# 200_watts_standard_cool_dip.net
KiCad netlist of a schematic drawn in EAGLE
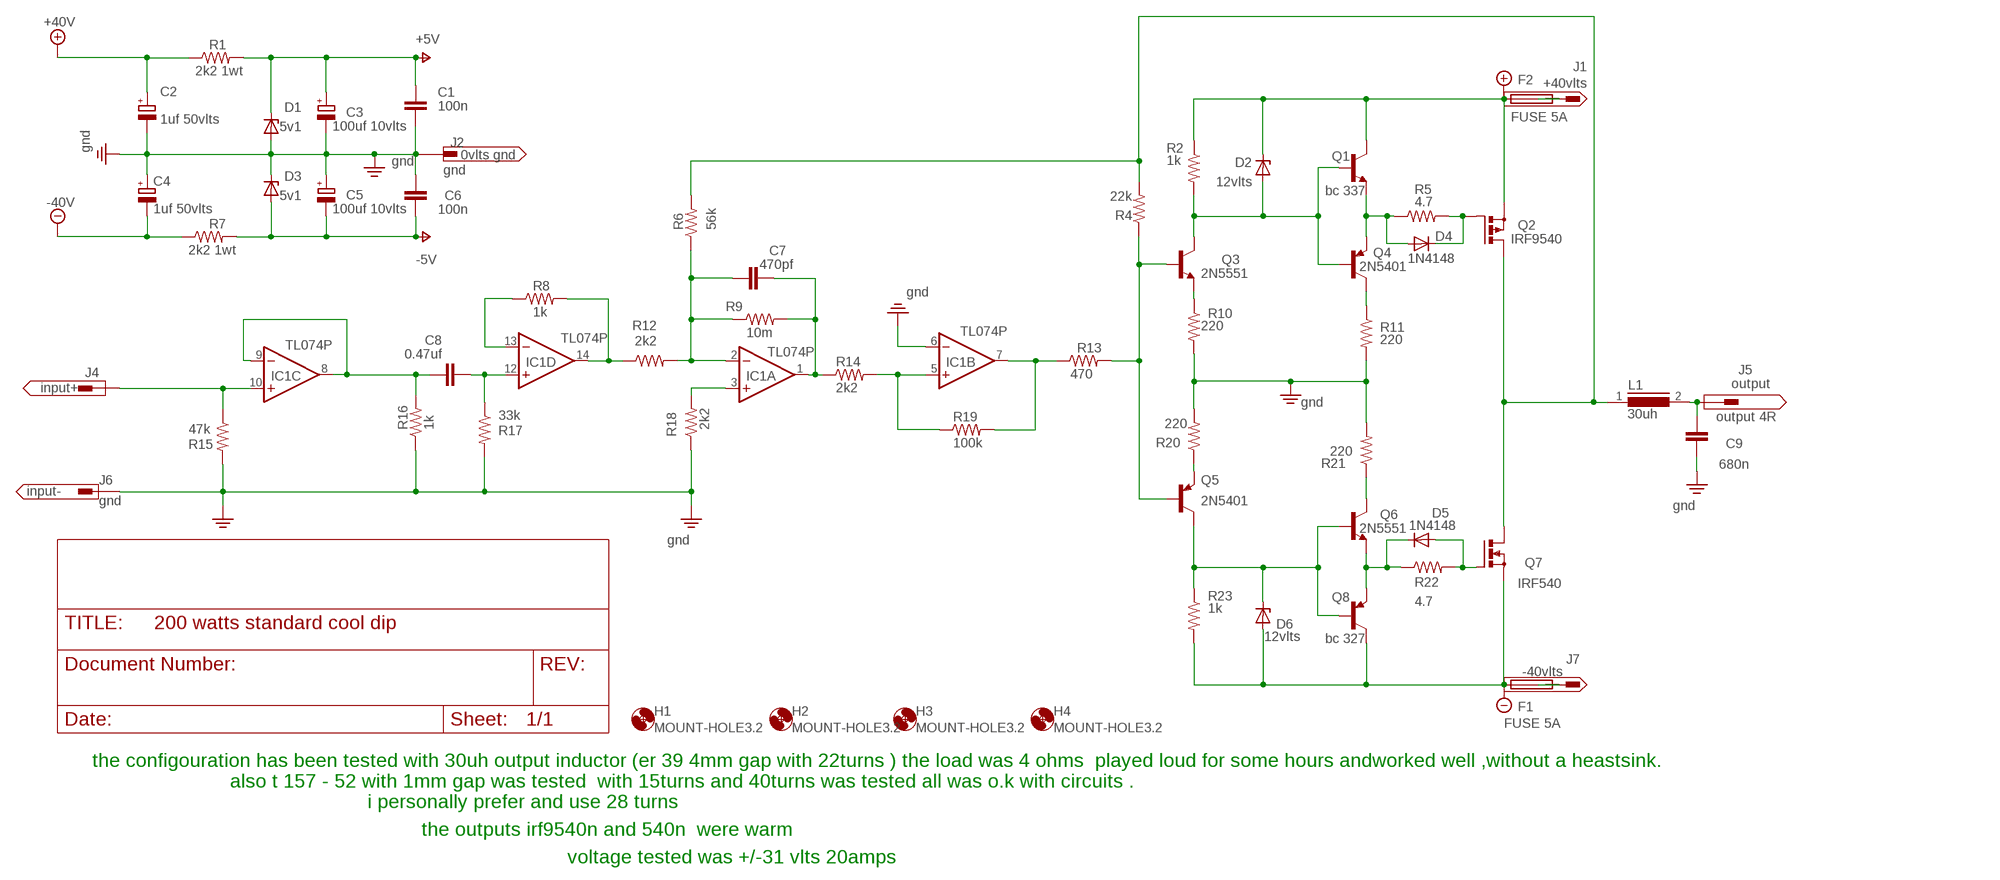
[diagram p0: schematic, sheet 1]

(export (version "E")
  (design (tool "Eeschema 10.0.6"))
  (components
    (comp (ref "C1")
      (value "100n")
      (footprint "eagle-import:C7.5B5")
      (libsource (lib "eagle-import") (part "C7.5/5"))
    )
    (comp (ref "C2")
      (value "1uf 50vlts")
      (footprint "eagle-import:E2,5-6")
      (libsource (lib "eagle-import") (part "CPOL-EUE2.5-6"))
    )
    (comp (ref "C3")
      (value "100uf 10vlts")
      (footprint "eagle-import:E3,5-8")
      (libsource (lib "eagle-import") (part "CPOL-EUE3.5-8"))
    )
    (comp (ref "C4")
      (value "1uf 50vlts")
      (footprint "eagle-import:E2,5-6")
      (libsource (lib "eagle-import") (part "CPOL-EUE2.5-6"))
    )
    (comp (ref "C5")
      (value "100uf 10vlts")
      (footprint "eagle-import:E3,5-8")
      (libsource (lib "eagle-import") (part "CPOL-EUE3.5-8"))
    )
    (comp (ref "C6")
      (value "100n")
      (footprint "eagle-import:C7.5B5")
      (libsource (lib "eagle-import") (part "C7.5/5"))
    )
    (comp (ref "C7")
      (value "470pf")
      (footprint "eagle-import:C5B3.5")
      (libsource (lib "eagle-import") (part "C5/3.5"))
    )
    (comp (ref "C8")
      (value "0.47uf")
      (footprint "eagle-import:C7.5B6")
      (libsource (lib "eagle-import") (part "C7.5/6"))
    )
    (comp (ref "C9")
      (value "680n")
      (footprint "eagle-import:C15B6")
      (libsource (lib "eagle-import") (part "C15/6"))
    )
    (comp (ref "D1")
      (value "5v1")
      (footprint "eagle-import:DO34Z7")
      (libsource (lib "eagle-import") (part "ZENER-DIODEDO34-7"))
    )
    (comp (ref "D2")
      (value "12vlts")
      (footprint "eagle-import:DO34Z7")
      (libsource (lib "eagle-import") (part "ZENER-DIODEDO34-7"))
    )
    (comp (ref "D3")
      (value "5v1")
      (footprint "eagle-import:DO34Z7")
      (libsource (lib "eagle-import") (part "ZENER-DIODEDO34-7"))
    )
    (comp (ref "D4")
      (value "1N4148")
      (footprint "eagle-import:DO35-7")
      (libsource (lib "eagle-import") (part "1N4148DO35-7"))
    )
    (comp (ref "D5")
      (value "1N4148")
      (footprint "eagle-import:DO35-7")
      (libsource (lib "eagle-import") (part "1N4148DO35-7"))
    )
    (comp (ref "D6")
      (value "12vlts")
      (footprint "eagle-import:DO34Z7")
      (libsource (lib "eagle-import") (part "ZENER-DIODEDO34-7"))
    )
    (comp (ref "F1")
      (value "FUSE 5A")
      (footprint "eagle-import:SHK20L")
      (libsource (lib "eagle-import") (part "FUSESHK20L"))
    )
    (comp (ref "F2")
      (value "FUSE 5A")
      (footprint "eagle-import:SHK20L")
      (libsource (lib "eagle-import") (part "FUSESHK20L"))
    )
    (comp (ref "H1")
      (value "MOUNT-HOLE3.2")
      (footprint "eagle-import:3,2")
      (libsource (lib "eagle-import") (part "MOUNT-HOLE3.2"))
    )
    (comp (ref "H2")
      (value "MOUNT-HOLE3.2")
      (footprint "eagle-import:3,2")
      (libsource (lib "eagle-import") (part "MOUNT-HOLE3.2"))
    )
    (comp (ref "H3")
      (value "MOUNT-HOLE3.2")
      (footprint "eagle-import:3,2")
      (libsource (lib "eagle-import") (part "MOUNT-HOLE3.2"))
    )
    (comp (ref "H4")
      (value "MOUNT-HOLE3.2")
      (footprint "eagle-import:3,2")
      (libsource (lib "eagle-import") (part "MOUNT-HOLE3.2"))
    )
    (comp (ref "IC1")
      (value "TL074P")
      (footprint "eagle-import:DIL14")
      (libsource (lib "eagle-import") (part "TL074P"))
    )
    (comp (ref "J1")
      (value "+40v")
      (footprint "eagle-import:F061.040")
      (fields (field (name "OC_FARNELL") "unknown") (field (name "OC_NEWARK") "unknown"))
      (libsource (lib "eagle-import") (part "PIN2F061.040"))
    )
    (comp (ref "J2")
      (value "gnd")
      (footprint "eagle-import:F061.040")
      (fields (field (name "OC_FARNELL") "unknown") (field (name "OC_NEWARK") "unknown"))
      (libsource (lib "eagle-import") (part "PIN2F061.040"))
    )
    (comp (ref "J4")
      (value "input")
      (footprint "eagle-import:F061.040")
      (fields (field (name "OC_FARNELL") "unknown") (field (name "OC_NEWARK") "unknown"))
      (libsource (lib "eagle-import") (part "PIN2F061.040"))
    )
    (comp (ref "J5")
      (value "output")
      (footprint "eagle-import:F061.040")
      (fields (field (name "OC_FARNELL") "unknown") (field (name "OC_NEWARK") "unknown"))
      (libsource (lib "eagle-import") (part "PIN2F061.040"))
    )
    (comp (ref "J6")
      (value "gnd")
      (footprint "eagle-import:F061.040")
      (fields (field (name "OC_FARNELL") "unknown") (field (name "OC_NEWARK") "unknown"))
      (libsource (lib "eagle-import") (part "PIN2F061.040"))
    )
    (comp (ref "J7")
      (value "-40v")
      (footprint "eagle-import:F061.040")
      (fields (field (name "OC_FARNELL") "unknown") (field (name "OC_NEWARK") "unknown"))
      (libsource (lib "eagle-import") (part "PIN2F061.040"))
    )
    (comp (ref "L1")
      (value "30uh")
      (footprint "eagle-import:SUKW1-17")
      (libsource (lib "eagle-import") (part "B82131"))
    )
    (comp (ref "Q1")
      (value "bc 337")
      (footprint "eagle-import:TO92-CBE")
      (libsource (lib "eagle-import") (part "-NPN-TO92-CBEBF393"))
    )
    (comp (ref "Q2")
      (value "IRF9540")
      (footprint "eagle-import:TO220BV")
      (libsource (lib "eagle-import") (part "PMOSFET_PTO220BV"))
    )
    (comp (ref "Q3")
      (value "2N5551")
      (footprint "eagle-import:TO92-EBC")
      (libsource (lib "eagle-import") (part "-NPN-TO92-EBCBC338-16"))
    )
    (comp (ref "Q4")
      (value "2N5401")
      (footprint "eagle-import:TO92-EBC")
      (libsource (lib "eagle-import") (part "-PNP-TO92-EBCBC327-25"))
    )
    (comp (ref "Q5")
      (value "2N5401")
      (footprint "eagle-import:TO92-EBC")
      (libsource (lib "eagle-import") (part "-PNP-TO92-EBCBC327-25"))
    )
    (comp (ref "Q6")
      (value "2N5551")
      (footprint "eagle-import:TO92-EBC")
      (libsource (lib "eagle-import") (part "-NPN-TO92-EBCBC338-16"))
    )
    (comp (ref "Q7")
      (value "IRF540")
      (footprint "eagle-import:TO220BV")
      (libsource (lib "eagle-import") (part "PMOSFET_NTO220BV"))
    )
    (comp (ref "Q8")
      (value "bc 327")
      (footprint "eagle-import:TO92-CBE")
      (libsource (lib "eagle-import") (part "-PNP-TO92-CBEBF493S"))
    )
    (comp (ref "R1")
      (value "2k2 1wt")
      (footprint "eagle-import:0309_12")
      (libsource (lib "eagle-import") (part "R-US_0309/12"))
    )
    (comp (ref "R2")
      (value "1k")
      (footprint "eagle-import:0207_7")
      (libsource (lib "eagle-import") (part "R-US_0207/7"))
    )
    (comp (ref "R4")
      (value "22k")
      (footprint "eagle-import:0207_7")
      (libsource (lib "eagle-import") (part "R-US_0207/7"))
    )
    (comp (ref "R5")
      (value "4.7")
      (footprint "eagle-import:0207_7")
      (libsource (lib "eagle-import") (part "R-US_0207/7"))
    )
    (comp (ref "R6")
      (value "56k")
      (footprint "eagle-import:0207_7")
      (libsource (lib "eagle-import") (part "R-US_0207/7"))
    )
    (comp (ref "R7")
      (value "2k2 1wt")
      (footprint "eagle-import:0309_12")
      (libsource (lib "eagle-import") (part "R-US_0309/12"))
    )
    (comp (ref "R8")
      (value "1k")
      (footprint "eagle-import:0207_2V")
      (libsource (lib "eagle-import") (part "R-US_0207/2V"))
    )
    (comp (ref "R9")
      (value "10m")
      (footprint "eagle-import:0207_2V")
      (libsource (lib "eagle-import") (part "R-US_0207/2V"))
    )
    (comp (ref "R10")
      (value "220")
      (footprint "eagle-import:0207_7")
      (libsource (lib "eagle-import") (part "R-US_0207/7"))
    )
    (comp (ref "R11")
      (value "220")
      (footprint "eagle-import:0207_7")
      (libsource (lib "eagle-import") (part "R-US_0207/7"))
    )
    (comp (ref "R12")
      (value "2k2")
      (footprint "eagle-import:0207_7")
      (libsource (lib "eagle-import") (part "R-US_0207/7"))
    )
    (comp (ref "R13")
      (value "470")
      (footprint "eagle-import:0207_7")
      (libsource (lib "eagle-import") (part "R-US_0207/7"))
    )
    (comp (ref "R14")
      (value "2k2")
      (footprint "eagle-import:0207_10")
      (libsource (lib "eagle-import") (part "R-US_0207/10"))
    )
    (comp (ref "R15")
      (value "47k")
      (footprint "eagle-import:0207_2V")
      (libsource (lib "eagle-import") (part "R-US_0207/2V"))
    )
    (comp (ref "R16")
      (value "1k")
      (footprint "eagle-import:0207_7")
      (libsource (lib "eagle-import") (part "R-US_0207/7"))
    )
    (comp (ref "R17")
      (value "33k")
      (footprint "eagle-import:0207_2V")
      (libsource (lib "eagle-import") (part "R-US_0207/2V"))
    )
    (comp (ref "R18")
      (value "2k2")
      (footprint "eagle-import:0207_7")
      (libsource (lib "eagle-import") (part "R-US_0207/7"))
    )
    (comp (ref "R19")
      (value "100k")
      (footprint "eagle-import:0207_5V")
      (libsource (lib "eagle-import") (part "R-US_0207/5V"))
    )
    (comp (ref "R20")
      (value "220")
      (footprint "eagle-import:0207_7")
      (libsource (lib "eagle-import") (part "R-US_0207/7"))
    )
    (comp (ref "R21")
      (value "220")
      (footprint "eagle-import:0207_7")
      (libsource (lib "eagle-import") (part "R-US_0207/7"))
    )
    (comp (ref "R22")
      (value "4.7")
      (footprint "eagle-import:0207_7")
      (libsource (lib "eagle-import") (part "R-US_0207/7"))
    )
    (comp (ref "R23")
      (value "1k")
      (footprint "eagle-import:0207_7")
      (libsource (lib "eagle-import") (part "R-US_0207/7"))
    )
  )
  (nets
    (net (code "1") (name "+5V") (class "Default")
      (node (ref "C1") (pin "1") (pinfunction "1_1") (pintype "passive"))
      (node (ref "C3") (pin "+") (pinfunction "+_+") (pintype "passive"))
      (node (ref "D1") (pin "C") (pinfunction "C_C") (pintype "passive"))
      (node (ref "R1") (pin "2") (pinfunction "2_2") (pintype "passive"))
    )
    (net (code "2") (name "+40V") (class "Default")
      (node (ref "C2") (pin "+") (pinfunction "+_+") (pintype "passive"))
      (node (ref "D2") (pin "C") (pinfunction "C_C") (pintype "passive"))
      (node (ref "F2") (pin "1A") (pinfunction "1_1A") (pintype "passive"))
      (node (ref "Q1") (pin "C") (pinfunction "C_C") (pintype "passive"))
      (node (ref "Q2") (pin "S") (pinfunction "S_S") (pintype "passive"))
      (node (ref "R1") (pin "1") (pinfunction "1_1") (pintype "passive"))
      (node (ref "R2") (pin "1") (pinfunction "1_1") (pintype "passive"))
    )
    (net (code "3") (name "-5V") (class "Default")
      (node (ref "C5") (pin "-") (pinfunction "-_-") (pintype "passive"))
      (node (ref "C6") (pin "2") (pinfunction "2_2") (pintype "passive"))
      (node (ref "D3") (pin "A") (pinfunction "A_A") (pintype "passive"))
      (node (ref "R7") (pin "2") (pinfunction "2_2") (pintype "passive"))
    )
    (net (code "4") (name "-40V") (class "Default")
      (node (ref "C4") (pin "-") (pinfunction "-_-") (pintype "passive"))
      (node (ref "D6") (pin "A") (pinfunction "A_A") (pintype "passive"))
      (node (ref "F1") (pin "1A") (pinfunction "1_1A") (pintype "passive"))
      (node (ref "Q7") (pin "S") (pinfunction "S_S") (pintype "passive"))
      (node (ref "Q8") (pin "C") (pinfunction "C_C") (pintype "passive"))
      (node (ref "R23") (pin "2") (pinfunction "2_2") (pintype "passive"))
      (node (ref "R7") (pin "1") (pinfunction "1_1") (pintype "passive"))
    )
    (net (code "5") (name "Net-(C9-Pad2)") (class "Default")
      (node (ref "C9") (pin "2") (pinfunction "2_2") (pintype "passive"))
      (node (ref "J5") (pin "A1") (pinfunction "1_A1") (pintype "passive"))
      (node (ref "J5") (pin "A2") (pinfunction "1_A2") (pintype "passive"))
      (node (ref "L1") (pin "2") (pinfunction "2_2") (pintype "passive"))
    )
    (net (code "6") (name "Net-(D2-PadA)") (class "Default")
      (node (ref "D2") (pin "A") (pinfunction "A_A") (pintype "passive"))
      (node (ref "Q1") (pin "B") (pinfunction "B_B") (pintype "passive"))
      (node (ref "Q3") (pin "C") (pinfunction "C_C") (pintype "passive"))
      (node (ref "Q4") (pin "B") (pinfunction "B_B") (pintype "passive"))
      (node (ref "R2") (pin "2") (pinfunction "2_2") (pintype "passive"))
    )
    (net (code "7") (name "Net-(D4-PadA)") (class "Default")
      (node (ref "D4") (pin "A") (pinfunction "A_A") (pintype "passive"))
      (node (ref "Q1") (pin "E") (pinfunction "E_E") (pintype "passive"))
      (node (ref "Q4") (pin "E") (pinfunction "E_E") (pintype "passive"))
      (node (ref "R5") (pin "1") (pinfunction "1_1") (pintype "passive"))
    )
    (net (code "8") (name "Net-(D4-PadC)") (class "Default")
      (node (ref "D4") (pin "C") (pinfunction "C_C") (pintype "passive"))
      (node (ref "Q2") (pin "G") (pinfunction "G_G") (pintype "passive"))
      (node (ref "R5") (pin "2") (pinfunction "2_2") (pintype "passive"))
    )
    (net (code "9") (name "Net-(D5-PadA)") (class "Default")
      (node (ref "D5") (pin "A") (pinfunction "A_A") (pintype "passive"))
      (node (ref "Q7") (pin "G") (pinfunction "G_G") (pintype "passive"))
      (node (ref "R22") (pin "2") (pinfunction "2_2") (pintype "passive"))
    )
    (net (code "10") (name "Net-(D5-PadC)") (class "Default")
      (node (ref "D5") (pin "C") (pinfunction "C_C") (pintype "passive"))
      (node (ref "Q6") (pin "E") (pinfunction "E_E") (pintype "passive"))
      (node (ref "Q8") (pin "E") (pinfunction "E_E") (pintype "passive"))
      (node (ref "R22") (pin "1") (pinfunction "1_1") (pintype "passive"))
    )
    (net (code "11") (name "Net-(D6-PadC)") (class "Default")
      (node (ref "D6") (pin "C") (pinfunction "C_C") (pintype "passive"))
      (node (ref "Q5") (pin "C") (pinfunction "C_C") (pintype "passive"))
      (node (ref "Q6") (pin "B") (pinfunction "B_B") (pintype "passive"))
      (node (ref "Q8") (pin "B") (pinfunction "B_B") (pintype "passive"))
      (node (ref "R23") (pin "1") (pinfunction "1_1") (pintype "passive"))
    )
    (net (code "12") (name "Net-(F1-2)") (class "Default")
      (node (ref "F1") (pin "2A") (pinfunction "2_2A") (pintype "passive"))
      (node (ref "J7") (pin "A1") (pinfunction "1_A1") (pintype "passive"))
      (node (ref "J7") (pin "A2") (pinfunction "1_A2") (pintype "passive"))
    )
    (net (code "13") (name "Net-(F2-2)") (class "Default")
      (node (ref "F2") (pin "2A") (pinfunction "2_2A") (pintype "passive"))
      (node (ref "J1") (pin "A1") (pinfunction "1_A1") (pintype "passive"))
      (node (ref "J1") (pin "A2") (pinfunction "1_A2") (pintype "passive"))
    )
    (net (code "14") (name "Net-(IC1A-+IN)") (class "Default")
      (node (ref "IC1") (pin "3") (pinfunction "+IN_3") (pintype "input"))
      (node (ref "R18") (pin "2") (pinfunction "2_2") (pintype "passive"))
    )
    (net (code "15") (name "Net-(IC1A--IN)") (class "Default")
      (node (ref "C7") (pin "1") (pinfunction "1_1") (pintype "passive"))
      (node (ref "IC1") (pin "2") (pinfunction "-IN_2") (pintype "input"))
      (node (ref "R12") (pin "2") (pinfunction "2_2") (pintype "passive"))
      (node (ref "R6") (pin "1") (pinfunction "1_1") (pintype "passive"))
      (node (ref "R9") (pin "1") (pinfunction "1_1") (pintype "passive"))
    )
    (net (code "16") (name "Net-(IC1A-OUT)") (class "Default")
      (node (ref "C7") (pin "2") (pinfunction "2_2") (pintype "passive"))
      (node (ref "IC1") (pin "1") (pinfunction "OUT_1") (pintype "output"))
      (node (ref "R14") (pin "1") (pinfunction "1_1") (pintype "passive"))
      (node (ref "R9") (pin "2") (pinfunction "2_2") (pintype "passive"))
    )
    (net (code "17") (name "Net-(IC1B-+IN)") (class "Default")
      (node (ref "IC1") (pin "5") (pinfunction "+IN_5") (pintype "input"))
      (node (ref "R14") (pin "2") (pinfunction "2_2") (pintype "passive"))
      (node (ref "R19") (pin "1") (pinfunction "1_1") (pintype "passive"))
    )
    (net (code "18") (name "Net-(IC1B-OUT)") (class "Default")
      (node (ref "IC1") (pin "7") (pinfunction "OUT_7") (pintype "output"))
      (node (ref "R13") (pin "1") (pinfunction "1_1") (pintype "passive"))
      (node (ref "R19") (pin "2") (pinfunction "2_2") (pintype "passive"))
    )
    (net (code "19") (name "Net-(IC1C-+IN)") (class "Default")
      (node (ref "IC1") (pin "10") (pinfunction "+IN_10") (pintype "input"))
      (node (ref "J4") (pin "A1") (pinfunction "1_A1") (pintype "passive"))
      (node (ref "J4") (pin "A2") (pinfunction "1_A2") (pintype "passive"))
      (node (ref "R15") (pin "1") (pinfunction "1_1") (pintype "passive"))
    )
    (net (code "20") (name "Net-(IC1C--IN)") (class "Default")
      (node (ref "C8") (pin "1") (pinfunction "1_1") (pintype "passive"))
      (node (ref "IC1") (pin "8") (pinfunction "OUT_8") (pintype "output"))
      (node (ref "IC1") (pin "9") (pinfunction "-IN_9") (pintype "input"))
      (node (ref "R16") (pin "2") (pinfunction "2_2") (pintype "passive"))
    )
    (net (code "21") (name "Net-(IC1D-+IN)") (class "Default")
      (node (ref "C8") (pin "2") (pinfunction "2_2") (pintype "passive"))
      (node (ref "IC1") (pin "12") (pinfunction "+IN_12") (pintype "input"))
      (node (ref "R17") (pin "1") (pinfunction "1_1") (pintype "passive"))
    )
    (net (code "22") (name "Net-(IC1D--IN)") (class "Default")
      (node (ref "IC1") (pin "13") (pinfunction "-IN_13") (pintype "input"))
      (node (ref "R8") (pin "1") (pinfunction "1_1") (pintype "passive"))
    )
    (net (code "23") (name "Net-(IC1D-OUT)") (class "Default")
      (node (ref "IC1") (pin "14") (pinfunction "OUT_14") (pintype "output"))
      (node (ref "R12") (pin "1") (pinfunction "1_1") (pintype "passive"))
      (node (ref "R8") (pin "2") (pinfunction "2_2") (pintype "passive"))
    )
    (net (code "24") (name "Net-(L1-Pad1)") (class "Default")
      (node (ref "L1") (pin "1") (pinfunction "1_1") (pintype "passive"))
      (node (ref "Q2") (pin "D") (pinfunction "D_D") (pintype "passive"))
      (node (ref "Q7") (pin "D") (pinfunction "D_D") (pintype "passive"))
      (node (ref "R4") (pin "2") (pinfunction "2_2") (pintype "passive"))
      (node (ref "R6") (pin "2") (pinfunction "2_2") (pintype "passive"))
    )
    (net (code "25") (name "Net-(Q3-PadB)") (class "Default")
      (node (ref "Q3") (pin "B") (pinfunction "B_B") (pintype "passive"))
      (node (ref "Q5") (pin "B") (pinfunction "B_B") (pintype "passive"))
      (node (ref "R13") (pin "2") (pinfunction "2_2") (pintype "passive"))
      (node (ref "R4") (pin "1") (pinfunction "1_1") (pintype "passive"))
    )
    (net (code "26") (name "Net-(Q3-PadE)") (class "Default")
      (node (ref "Q3") (pin "E") (pinfunction "E_E") (pintype "passive"))
      (node (ref "R10") (pin "1") (pinfunction "1_1") (pintype "passive"))
    )
    (net (code "27") (name "Net-(Q4-PadC)") (class "Default")
      (node (ref "Q4") (pin "C") (pinfunction "C_C") (pintype "passive"))
      (node (ref "R11") (pin "1") (pinfunction "1_1") (pintype "passive"))
    )
    (net (code "28") (name "Net-(Q5-PadE)") (class "Default")
      (node (ref "Q5") (pin "E") (pinfunction "E_E") (pintype "passive"))
      (node (ref "R20") (pin "1") (pinfunction "1_1") (pintype "passive"))
    )
    (net (code "29") (name "Net-(Q6-PadC)") (class "Default")
      (node (ref "Q6") (pin "C") (pinfunction "C_C") (pintype "passive"))
      (node (ref "R21") (pin "1") (pinfunction "1_1") (pintype "passive"))
    )
    (net (code "30") (name "gnd") (class "Default")
      (node (ref "C1") (pin "2") (pinfunction "2_2") (pintype "passive"))
      (node (ref "C2") (pin "-") (pinfunction "-_-") (pintype "passive"))
      (node (ref "C3") (pin "-") (pinfunction "-_-") (pintype "passive"))
      (node (ref "C4") (pin "+") (pinfunction "+_+") (pintype "passive"))
      (node (ref "C5") (pin "+") (pinfunction "+_+") (pintype "passive"))
      (node (ref "C6") (pin "1") (pinfunction "1_1") (pintype "passive"))
      (node (ref "C9") (pin "1") (pinfunction "1_1") (pintype "passive"))
      (node (ref "D1") (pin "A") (pinfunction "A_A") (pintype "passive"))
      (node (ref "D3") (pin "C") (pinfunction "C_C") (pintype "passive"))
      (node (ref "IC1") (pin "6") (pinfunction "-IN_6") (pintype "input"))
      (node (ref "J2") (pin "A1") (pinfunction "1_A1") (pintype "passive"))
      (node (ref "J2") (pin "A2") (pinfunction "1_A2") (pintype "passive"))
      (node (ref "J6") (pin "A1") (pinfunction "1_A1") (pintype "passive"))
      (node (ref "J6") (pin "A2") (pinfunction "1_A2") (pintype "passive"))
      (node (ref "R10") (pin "2") (pinfunction "2_2") (pintype "passive"))
      (node (ref "R11") (pin "2") (pinfunction "2_2") (pintype "passive"))
      (node (ref "R15") (pin "2") (pinfunction "2_2") (pintype "passive"))
      (node (ref "R16") (pin "1") (pinfunction "1_1") (pintype "passive"))
      (node (ref "R17") (pin "2") (pinfunction "2_2") (pintype "passive"))
      (node (ref "R18") (pin "1") (pinfunction "1_1") (pintype "passive"))
      (node (ref "R20") (pin "2") (pinfunction "2_2") (pintype "passive"))
      (node (ref "R21") (pin "2") (pinfunction "2_2") (pintype "passive"))
    )
  )
)
